# FPGA.net
KiCad netlist of a schematic drawn in Altium Designer
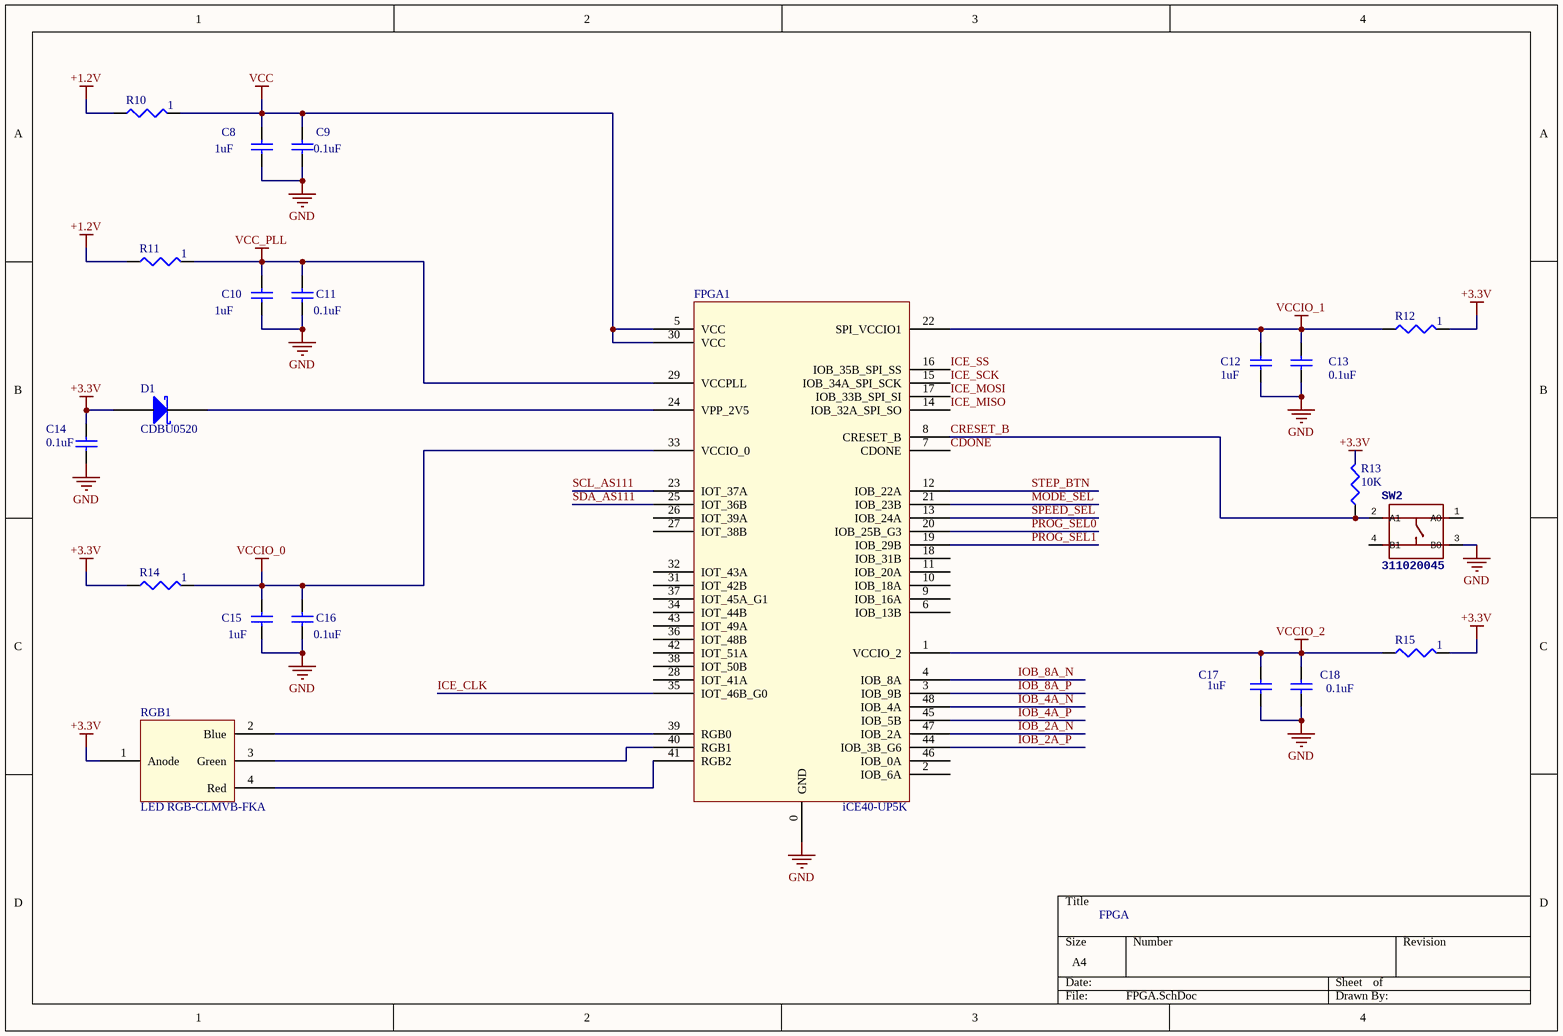
[diagram p0: FPGA.SchDoc]

(export (version "E")
  (design (tool "Eeschema 10.0.6"))
  (components
    (comp (ref "C8")
      (value "1uF")
      (footprint "C0402")
      (description "Capacitor (Semiconductor SIM Model)")
      (fields
        (field (name "MANUFACTURER") "TDK Corporation")
        (field (name "MANUFACTURER PART NUMBER") "CGB2A1JB1E105M033BC")
        (field (name "PUBLISHER") "Altium Limited")
      )
      (libsource (lib "Miscellaneous Devices") (part "Cap Semi"))
    )
    (comp (ref "C9")
      (value "0.1uF")
      (footprint "C0402")
      (description "Capacitor (Semiconductor SIM Model)")
      (fields
        (field (name "MANUFACTURER") "Samsung Electro-Mechanics")
        (field (name "MANUFACTURER PART NUMBER") "CL05B104KA5NNNC")
        (field (name "PUBLISHER") "Altium Limited")
      )
      (libsource (lib "Miscellaneous Devices") (part "Cap Semi"))
    )
    (comp (ref "C10")
      (value "1uF")
      (footprint "C0402")
      (description "Capacitor (Semiconductor SIM Model)")
      (fields
        (field (name "MANUFACTURER") "TDK Corporation")
        (field (name "MANUFACTURER PART NUMBER") "CGB2A1JB1E105M033BC")
        (field (name "PUBLISHER") "Altium Limited")
      )
      (libsource (lib "Miscellaneous Devices") (part "Cap Semi"))
    )
    (comp (ref "C11")
      (value "0.1uF")
      (footprint "C0402")
      (description "Capacitor (Semiconductor SIM Model)")
      (fields
        (field (name "MANUFACTURER") "Samsung Electro-Mechanics")
        (field (name "MANUFACTURER PART NUMBER") "CL05B104KA5NNNC")
        (field (name "PUBLISHER") "Altium Limited")
      )
      (libsource (lib "Miscellaneous Devices") (part "Cap Semi"))
    )
    (comp (ref "C12")
      (value "1uF")
      (footprint "C0402")
      (description "Capacitor (Semiconductor SIM Model)")
      (fields
        (field (name "MANUFACTURER") "TDK Corporation")
        (field (name "MANUFACTURER PART NUMBER") "CGB2A1JB1E105M033BC")
        (field (name "PUBLISHER") "Altium Limited")
      )
      (libsource (lib "Miscellaneous Devices") (part "Cap Semi"))
    )
    (comp (ref "C13")
      (value "0.1uF")
      (footprint "C0402")
      (description "Capacitor (Semiconductor SIM Model)")
      (fields
        (field (name "MANUFACTURER") "Samsung Electro-Mechanics")
        (field (name "MANUFACTURER PART NUMBER") "CL05B104KA5NNNC")
        (field (name "PUBLISHER") "Altium Limited")
      )
      (libsource (lib "Miscellaneous Devices") (part "Cap Semi"))
    )
    (comp (ref "C14")
      (value "0.1uF")
      (footprint "C0402")
      (description "Capacitor (Semiconductor SIM Model)")
      (fields
        (field (name "MANUFACTURER") "Samsung Electro-Mechanics")
        (field (name "MANUFACTURER PART NUMBER") "CL05B104KA5NNNC")
        (field (name "PUBLISHER") "Altium Limited")
      )
      (libsource (lib "Miscellaneous Devices") (part "Cap Semi"))
    )
    (comp (ref "C15")
      (value "1uF")
      (footprint "C0402")
      (description "Capacitor (Semiconductor SIM Model)")
      (fields
        (field (name "MANUFACTURER") "TDK Corporation")
        (field (name "MANUFACTURER PART NUMBER") "CGB2A1JB1E105M033BC")
        (field (name "PUBLISHER") "Altium Limited")
      )
      (libsource (lib "Miscellaneous Devices") (part "Cap Semi"))
    )
    (comp (ref "C16")
      (value "0.1uF")
      (footprint "C0402")
      (description "Capacitor (Semiconductor SIM Model)")
      (fields
        (field (name "MANUFACTURER") "Samsung Electro-Mechanics")
        (field (name "MANUFACTURER PART NUMBER") "CL05B104KA5NNNC")
        (field (name "PUBLISHER") "Altium Limited")
      )
      (libsource (lib "Miscellaneous Devices") (part "Cap Semi"))
    )
    (comp (ref "C17")
      (value "1uF")
      (footprint "C0402")
      (description "Capacitor (Semiconductor SIM Model)")
      (fields
        (field (name "MANUFACTURER") "TDK Corporation")
        (field (name "MANUFACTURER PART NUMBER") "CGB2A1JB1E105M033BC")
        (field (name "PUBLISHER") "Altium Limited")
      )
      (libsource (lib "Miscellaneous Devices") (part "Cap Semi"))
    )
    (comp (ref "C18")
      (value "0.1uF")
      (footprint "C0402")
      (description "Capacitor (Semiconductor SIM Model)")
      (fields
        (field (name "MANUFACTURER") "Samsung Electro-Mechanics")
        (field (name "MANUFACTURER PART NUMBER") "CL05B104KA5NNNC")
        (field (name "PUBLISHER") "Altium Limited")
      )
      (libsource (lib "Miscellaneous Devices") (part "Cap Semi"))
    )
    (comp (ref "D1")
      (value "CDBU0520")
      (footprint "CDBU0520")
      (description "DIODE SCHOTTKY 20V 500MA 0603")
      (fields (field (name "MANUFACTURER") "Comchip Technology"))
      (libsource (lib "FPGAlib") (part "CDBU0520"))
    )
    (comp (ref "FPGA1")
      (value "iCE40-UP5K")
      (footprint "SLAB-QFN48-7X7-MD")
      (description "iCE40-UP5K FPGA")
      (fields
        (field (name "MANUFACTURER") "Lattice Semiconductor Corporation")
        (field (name "MANUFACTURER PART NUMBER") "ICE40UP5K-SG48ITR50")
      )
      (libsource (lib "FPGAlib") (part "iCE40-UP5K FPGA"))
    )
    (comp (ref "R10")
      (value "1")
      (footprint "R0402")
      (description "Resistor")
      (fields
        (field (name "MANUFACTURER") "Yageo")
        (field (name "MANUFACTURER PART NUMBER") "AC0402JR-071RL")
        (field (name "PUBLISHER") "Altium Limited")
      )
      (libsource (lib "Miscellaneous Devices") (part "Res3"))
    )
    (comp (ref "R11")
      (value "1")
      (footprint "R0402")
      (description "Resistor")
      (fields
        (field (name "MANUFACTURER") "Yageo")
        (field (name "MANUFACTURER PART NUMBER") "AC0402JR-071RL")
        (field (name "PUBLISHER") "Altium Limited")
      )
      (libsource (lib "Miscellaneous Devices") (part "Res3"))
    )
    (comp (ref "R12")
      (value "1")
      (footprint "R0402")
      (description "Resistor")
      (fields
        (field (name "MANUFACTURER") "Yageo")
        (field (name "MANUFACTURER PART NUMBER") "AC0402JR-071RL")
        (field (name "PUBLISHER") "Altium Limited")
      )
      (libsource (lib "Miscellaneous Devices") (part "Res3"))
    )
    (comp (ref "R13")
      (value "10K")
      (footprint "R0402")
      (description "Resistor")
      (fields
        (field (name "MANUFACTURER") "Yageo")
        (field (name "MANUFACTURER PART NUMBER") "RC0402JR-0710KP")
        (field (name "PUBLISHER") "Altium Limited")
      )
      (libsource (lib "Miscellaneous Devices") (part "Res3"))
    )
    (comp (ref "R14")
      (value "1")
      (footprint "R0402")
      (description "Resistor")
      (fields
        (field (name "MANUFACTURER") "Yageo")
        (field (name "MANUFACTURER PART NUMBER") "AC0402JR-071RL")
        (field (name "PUBLISHER") "Altium Limited")
      )
      (libsource (lib "Miscellaneous Devices") (part "Res3"))
    )
    (comp (ref "R15")
      (value "1")
      (footprint "R0402")
      (description "Resistor")
      (fields
        (field (name "MANUFACTURER") "Yageo")
        (field (name "MANUFACTURER PART NUMBER") "AC0402JR-071RL")
        (field (name "PUBLISHER") "Altium Limited")
      )
      (libsource (lib "Miscellaneous Devices") (part "Res3"))
    )
    (comp (ref "RGB1")
      (value "LED RGB-CLMVB-FKA")
      (footprint "ledRGB")
      (description "LED RGB CLEAR 4PLCC SMD")
      (fields
        (field (name "MANUFACTURER") "Cree Inc.")
        (field (name "MANUFACTURER PART NUMBER") "CLMVC-FKA-CL1D1L71BB7C3C3")
      )
      (libsource (lib "FPGAlib") (part "LED RGB-CLMVB-FKA"))
    )
    (comp (ref "SW2")
      (value "311020045")
      (footprint "SW4-SMD-4.2X3.2X2.5MM")
      (description "SWITCH TACTILE SPST-NO 0.05A 16V")
      (fields (field (name "MPN") "DHT-4235A") (field (name "MANUFACTURER") "C&K"))
      (libsource (lib "FPGAlib") (part "PTS810 SJM 250 SMTR LFS"))
    )
  )
  (nets
    (net (code "1") (name "+1.2V") (class "Default")
      (node (ref "R10") (pin "1") (pinfunction "1_1") (pintype "passive"))
      (node (ref "R11") (pin "1") (pinfunction "1_1") (pintype "passive"))
    )
    (net (code "2") (name "+3.3V") (class "Default")
      (node (ref "C14") (pin "2") (pinfunction "2_2") (pintype "passive"))
      (node (ref "D1") (pin "1") (pintype "passive"))
      (node (ref "R12") (pin "2") (pinfunction "2_2") (pintype "passive"))
      (node (ref "R13") (pin "2") (pinfunction "2_2") (pintype "passive"))
      (node (ref "R14") (pin "1") (pinfunction "1_1") (pintype "passive"))
      (node (ref "R15") (pin "2") (pinfunction "2_2") (pintype "passive"))
      (node (ref "RGB1") (pin "1") (pinfunction "Anode_1") (pintype "passive"))
    )
    (net (code "3") (name "/CDONE") (class "Default")
      (node (ref "FPGA1") (pin "7") (pinfunction "CDONE_7") (pintype "passive"))
    )
    (net (code "4") (name "/CRESET_B") (class "Default")
      (node (ref "FPGA1") (pin "8") (pinfunction "CRESET_B_8") (pintype "passive"))
      (node (ref "R13") (pin "1") (pinfunction "1_1") (pintype "passive"))
      (node (ref "SW2") (pin "2") (pinfunction "A1_2") (pintype "passive"))
    )
    (net (code "5") (name "/ICE_CLK") (class "Default")
      (node (ref "FPGA1") (pin "35") (pinfunction "IOT_46B_G0_35") (pintype "passive"))
    )
    (net (code "6") (name "/ICE_MISO") (class "Default")
      (node (ref "FPGA1") (pin "14") (pinfunction "IOB_32A_SPI_SO_14") (pintype "passive"))
    )
    (net (code "7") (name "/ICE_MOSI") (class "Default")
      (node (ref "FPGA1") (pin "17") (pinfunction "IOB_33B_SPI_SI_17") (pintype "passive"))
    )
    (net (code "8") (name "/ICE_SCK") (class "Default")
      (node (ref "FPGA1") (pin "15") (pinfunction "IOB_34A_SPI_SCK_15") (pintype "passive"))
    )
    (net (code "9") (name "/ICE_SS") (class "Default")
      (node (ref "FPGA1") (pin "16") (pinfunction "IOB_35B_SPI_SS_16") (pintype "passive"))
    )
    (net (code "10") (name "/IOB_2A_N") (class "Default")
      (node (ref "FPGA1") (pin "47") (pinfunction "IOB_2A_47") (pintype "passive"))
    )
    (net (code "11") (name "/IOB_2A_P") (class "Default")
      (node (ref "FPGA1") (pin "44") (pinfunction "IOB_3B_G6_44") (pintype "passive"))
    )
    (net (code "12") (name "/IOB_4A_N") (class "Default")
      (node (ref "FPGA1") (pin "48") (pinfunction "IOB_4A_48") (pintype "passive"))
    )
    (net (code "13") (name "/IOB_4A_P") (class "Default")
      (node (ref "FPGA1") (pin "45") (pinfunction "IOB_5B_45") (pintype "passive"))
    )
    (net (code "14") (name "/IOB_8A_N") (class "Default")
      (node (ref "FPGA1") (pin "4") (pinfunction "IOB_8A_4") (pintype "passive"))
    )
    (net (code "15") (name "/IOB_8A_P") (class "Default")
      (node (ref "FPGA1") (pin "3") (pinfunction "IOB_9B_3") (pintype "passive"))
    )
    (net (code "16") (name "/MODE_SEL") (class "Default")
      (node (ref "FPGA1") (pin "21") (pinfunction "IOB_23B_21") (pintype "passive"))
    )
    (net (code "17") (name "/PROG_SEL0") (class "Default")
      (node (ref "FPGA1") (pin "20") (pinfunction "IOB_25B_G3_20") (pintype "passive"))
    )
    (net (code "18") (name "/PROG_SEL1") (class "Default")
      (node (ref "FPGA1") (pin "19") (pinfunction "IOB_29B_19") (pintype "passive"))
    )
    (net (code "19") (name "/SCL_AS111") (class "Default")
      (node (ref "FPGA1") (pin "23") (pinfunction "IOT_37A_23") (pintype "passive"))
    )
    (net (code "20") (name "/SDA_AS111") (class "Default")
      (node (ref "FPGA1") (pin "25") (pinfunction "IOT_36B_25") (pintype "passive"))
    )
    (net (code "21") (name "/SPEED_SEL") (class "Default")
      (node (ref "FPGA1") (pin "13") (pinfunction "IOB_24A_13") (pintype "passive"))
    )
    (net (code "22") (name "/STEP_BTN") (class "Default")
      (node (ref "FPGA1") (pin "12") (pinfunction "IOB_22A_12") (pintype "passive"))
    )
    (net (code "23") (name "GND") (class "Default")
      (node (ref "C10") (pin "1") (pinfunction "1_1") (pintype "passive"))
      (node (ref "C11") (pin "1") (pinfunction "1_1") (pintype "passive"))
      (node (ref "C12") (pin "1") (pinfunction "1_1") (pintype "passive"))
      (node (ref "C13") (pin "1") (pinfunction "1_1") (pintype "passive"))
      (node (ref "C14") (pin "1") (pinfunction "1_1") (pintype "passive"))
      (node (ref "C15") (pin "1") (pinfunction "1_1") (pintype "passive"))
      (node (ref "C16") (pin "1") (pinfunction "1_1") (pintype "passive"))
      (node (ref "C17") (pin "1") (pinfunction "1_1") (pintype "passive"))
      (node (ref "C18") (pin "1") (pinfunction "1_1") (pintype "passive"))
      (node (ref "C8") (pin "1") (pinfunction "1_1") (pintype "passive"))
      (node (ref "C9") (pin "1") (pinfunction "1_1") (pintype "passive"))
      (node (ref "FPGA1") (pin "0") (pinfunction "GND_0") (pintype "passive"))
      (node (ref "SW2") (pin "3") (pinfunction "B0_3") (pintype "passive"))
    )
    (net (code "24") (name "Net-(FPGA1-RGB0)") (class "Default")
      (node (ref "FPGA1") (pin "39") (pinfunction "RGB0_39") (pintype "passive"))
      (node (ref "RGB1") (pin "2") (pinfunction "Blue_2") (pintype "passive"))
    )
    (net (code "25") (name "Net-(FPGA1-RGB1)") (class "Default")
      (node (ref "FPGA1") (pin "40") (pinfunction "RGB1_40") (pintype "passive"))
      (node (ref "RGB1") (pin "3") (pinfunction "Green_3") (pintype "passive"))
    )
    (net (code "26") (name "Net-(FPGA1-RGB2)") (class "Default")
      (node (ref "FPGA1") (pin "41") (pinfunction "RGB2_41") (pintype "passive"))
      (node (ref "RGB1") (pin "4") (pinfunction "Red_4") (pintype "passive"))
    )
    (net (code "27") (name "Net-(FPGA1-VPP_2V5)") (class "Default")
      (node (ref "D1") (pin "2") (pintype "passive"))
      (node (ref "FPGA1") (pin "24") (pinfunction "VPP_2V5_24") (pintype "passive"))
    )
    (net (code "28") (name "VCC") (class "Default")
      (node (ref "C8") (pin "2") (pinfunction "2_2") (pintype "passive"))
      (node (ref "C9") (pin "2") (pinfunction "2_2") (pintype "passive"))
      (node (ref "FPGA1") (pin "30") (pinfunction "VCC_30") (pintype "passive"))
      (node (ref "FPGA1") (pin "5") (pinfunction "VCC_5") (pintype "passive"))
      (node (ref "R10") (pin "2") (pinfunction "2_2") (pintype "passive"))
    )
    (net (code "29") (name "VCCIO_0") (class "Default")
      (node (ref "C15") (pin "2") (pinfunction "2_2") (pintype "passive"))
      (node (ref "C16") (pin "2") (pinfunction "2_2") (pintype "passive"))
      (node (ref "FPGA1") (pin "33") (pinfunction "VCCIO_0_33") (pintype "passive"))
      (node (ref "R14") (pin "2") (pinfunction "2_2") (pintype "passive"))
    )
    (net (code "30") (name "VCCIO_1") (class "Default")
      (node (ref "C12") (pin "2") (pinfunction "2_2") (pintype "passive"))
      (node (ref "C13") (pin "2") (pinfunction "2_2") (pintype "passive"))
      (node (ref "FPGA1") (pin "22") (pinfunction "SPI_VCCIO1_22") (pintype "passive"))
      (node (ref "R12") (pin "1") (pinfunction "1_1") (pintype "passive"))
    )
    (net (code "31") (name "VCCIO_2") (class "Default")
      (node (ref "C17") (pin "2") (pinfunction "2_2") (pintype "passive"))
      (node (ref "C18") (pin "2") (pinfunction "2_2") (pintype "passive"))
      (node (ref "FPGA1") (pin "1") (pinfunction "VCCIO_2_1") (pintype "passive"))
      (node (ref "R15") (pin "1") (pinfunction "1_1") (pintype "passive"))
    )
    (net (code "32") (name "VCC_PLL") (class "Default")
      (node (ref "C10") (pin "2") (pinfunction "2_2") (pintype "passive"))
      (node (ref "C11") (pin "2") (pinfunction "2_2") (pintype "passive"))
      (node (ref "FPGA1") (pin "29") (pinfunction "VCCPLL_29") (pintype "passive"))
      (node (ref "R11") (pin "2") (pinfunction "2_2") (pintype "passive"))
    )
    (net (code "33") (name "unconnected-(FPGA1-IOB_0A-Pad46)") (class "Default")
      (node (ref "FPGA1") (pin "46") (pinfunction "IOB_0A_46") (pintype "passive"))
    )
    (net (code "34") (name "unconnected-(FPGA1-IOB_6A-Pad2)") (class "Default")
      (node (ref "FPGA1") (pin "2") (pinfunction "IOB_6A_2") (pintype "passive"))
    )
    (net (code "35") (name "unconnected-(FPGA1-IOB_13B-Pad6)") (class "Default")
      (node (ref "FPGA1") (pin "6") (pinfunction "IOB_13B_6") (pintype "passive"))
    )
    (net (code "36") (name "unconnected-(FPGA1-IOB_16A-Pad9)") (class "Default")
      (node (ref "FPGA1") (pin "9") (pinfunction "IOB_16A_9") (pintype "passive"))
    )
    (net (code "37") (name "unconnected-(FPGA1-IOB_18A-Pad10)") (class "Default")
      (node (ref "FPGA1") (pin "10") (pinfunction "IOB_18A_10") (pintype "passive"))
    )
    (net (code "38") (name "unconnected-(FPGA1-IOB_20A-Pad11)") (class "Default")
      (node (ref "FPGA1") (pin "11") (pinfunction "IOB_20A_11") (pintype "passive"))
    )
    (net (code "39") (name "unconnected-(FPGA1-IOB_31B-Pad18)") (class "Default")
      (node (ref "FPGA1") (pin "18") (pinfunction "IOB_31B_18") (pintype "passive"))
    )
    (net (code "40") (name "unconnected-(FPGA1-IOT_38B-Pad27)") (class "Default")
      (node (ref "FPGA1") (pin "27") (pinfunction "IOT_38B_27") (pintype "passive"))
    )
    (net (code "41") (name "unconnected-(FPGA1-IOT_39A-Pad26)") (class "Default")
      (node (ref "FPGA1") (pin "26") (pinfunction "IOT_39A_26") (pintype "passive"))
    )
    (net (code "42") (name "unconnected-(FPGA1-IOT_41A-Pad28)") (class "Default")
      (node (ref "FPGA1") (pin "28") (pinfunction "IOT_41A_28") (pintype "passive"))
    )
    (net (code "43") (name "unconnected-(FPGA1-IOT_42B-Pad31)") (class "Default")
      (node (ref "FPGA1") (pin "31") (pinfunction "IOT_42B_31") (pintype "passive"))
    )
    (net (code "44") (name "unconnected-(FPGA1-IOT_43A-Pad32)") (class "Default")
      (node (ref "FPGA1") (pin "32") (pinfunction "IOT_43A_32") (pintype "passive"))
    )
    (net (code "45") (name "unconnected-(FPGA1-IOT_44B-Pad34)") (class "Default")
      (node (ref "FPGA1") (pin "34") (pinfunction "IOT_44B_34") (pintype "passive"))
    )
    (net (code "46") (name "unconnected-(FPGA1-IOT_45A_G1-Pad37)") (class "Default")
      (node (ref "FPGA1") (pin "37") (pinfunction "IOT_45A_G1_37") (pintype "passive"))
    )
    (net (code "47") (name "unconnected-(FPGA1-IOT_48B-Pad36)") (class "Default")
      (node (ref "FPGA1") (pin "36") (pinfunction "IOT_48B_36") (pintype "passive"))
    )
    (net (code "48") (name "unconnected-(FPGA1-IOT_49A-Pad43)") (class "Default")
      (node (ref "FPGA1") (pin "43") (pinfunction "IOT_49A_43") (pintype "passive"))
    )
    (net (code "49") (name "unconnected-(FPGA1-IOT_50B-Pad38)") (class "Default")
      (node (ref "FPGA1") (pin "38") (pinfunction "IOT_50B_38") (pintype "passive"))
    )
    (net (code "50") (name "unconnected-(FPGA1-IOT_51A-Pad42)") (class "Default")
      (node (ref "FPGA1") (pin "42") (pinfunction "IOT_51A_42") (pintype "passive"))
    )
    (net (code "51") (name "unconnected-(SW2-A0-Pad1)") (class "Default")
      (node (ref "SW2") (pin "1") (pinfunction "A0_1") (pintype "passive"))
    )
    (net (code "52") (name "unconnected-(SW2-B1-Pad4)") (class "Default")
      (node (ref "SW2") (pin "4") (pinfunction "B1_4") (pintype "passive"))
    )
  )
)
